# misc.net
KiCad netlist of a schematic drawn in Altium Designer
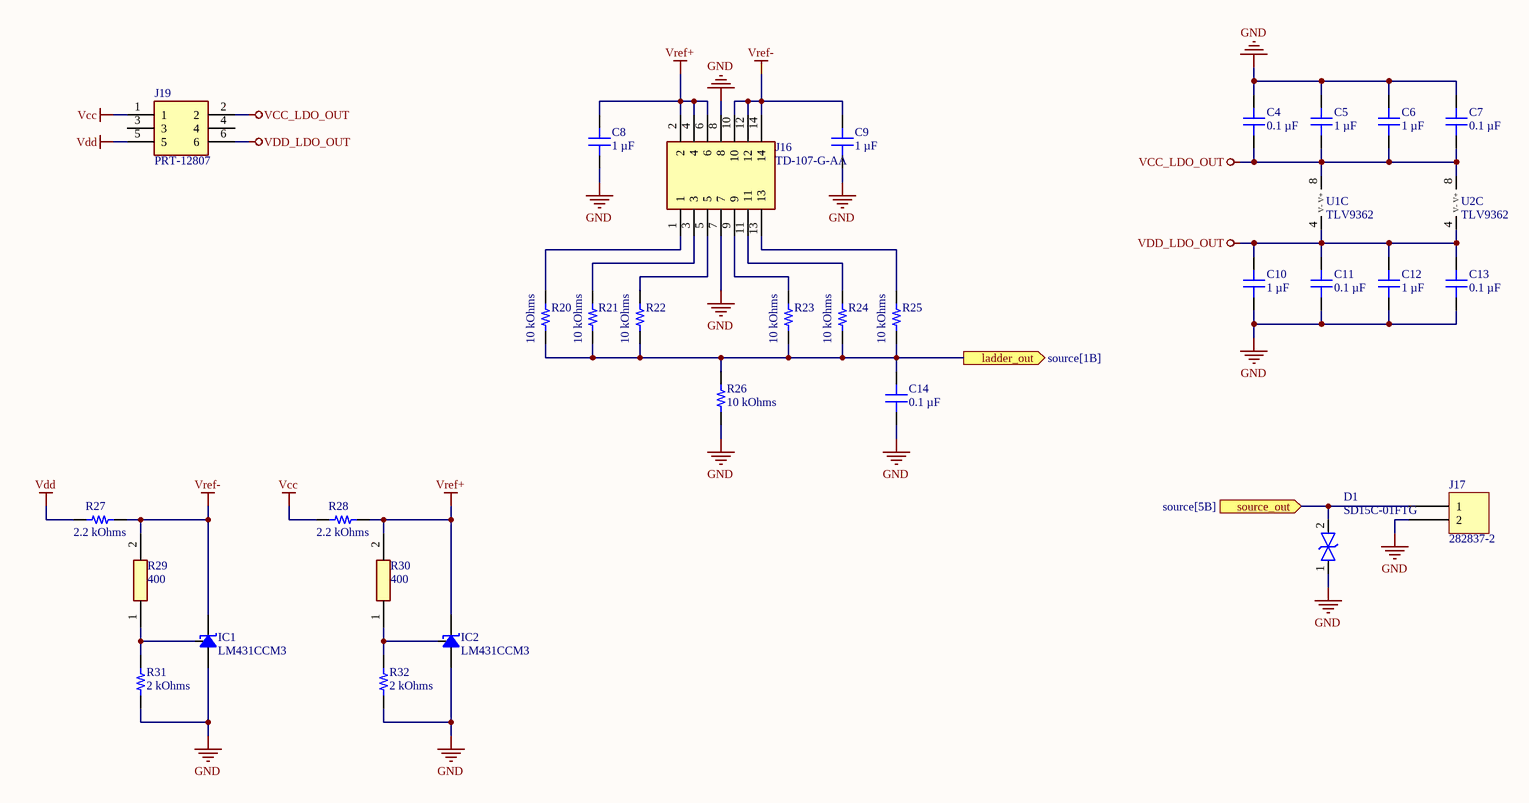
[diagram p0: misc.SchDoc]

(export (version "E")
  (design (tool "Eeschema 10.0.6"))
  (components
    (comp (ref "C4")
      (value "0.1 µF")
      (footprint "CAP 1206_3216 - 0.8MM")
      (description "CAP CER 0.1UF 50V X7R 1206")
      (fields
        (field (name "PART NUMBER") "885012208087")
        (field (name "CAPACITANCE") "0.1 µF")
        (field (name "MANUFACTURER") "Würth Elektronik")
      )
      (libsource (lib "Celestial Altium Library - altium_library") (part "Capacitor"))
    )
    (comp (ref "C5")
      (value "1 µF")
      (footprint "CAP 1206_3216 - 0.8MM")
      (description "CAP CER 1UF 50V X7R 1206")
      (fields
        (field (name "PART NUMBER") "885012208093")
        (field (name "CAPACITANCE") "1 µF")
        (field (name "MANUFACTURER") "Würth Elektronik")
      )
      (libsource (lib "Celestial Altium Library - altium_library") (part "Capacitor"))
    )
    (comp (ref "C6")
      (value "1 µF")
      (footprint "CAP 1206_3216 - 0.8MM")
      (description "CAP CER 1UF 50V X7R 1206")
      (fields
        (field (name "PART NUMBER") "885012208093")
        (field (name "CAPACITANCE") "1 µF")
        (field (name "MANUFACTURER") "Würth Elektronik")
      )
      (libsource (lib "Celestial Altium Library - altium_library") (part "Capacitor"))
    )
    (comp (ref "C7")
      (value "0.1 µF")
      (footprint "CAP 1206_3216 - 0.8MM")
      (description "CAP CER 0.1UF 50V X7R 1206")
      (fields
        (field (name "PART NUMBER") "885012208087")
        (field (name "CAPACITANCE") "0.1 µF")
        (field (name "MANUFACTURER") "Würth Elektronik")
      )
      (libsource (lib "Celestial Altium Library - altium_library") (part "Capacitor"))
    )
    (comp (ref "C8")
      (value "1 µF")
      (footprint "CAP 1206_3216 - 0.8MM")
      (description "CAP CER 1UF 50V X7R 1206")
      (fields
        (field (name "PART NUMBER") "885012208093")
        (field (name "CAPACITANCE") "1 µF")
        (field (name "MANUFACTURER") "Würth Elektronik")
      )
      (libsource (lib "Celestial Altium Library - altium_library") (part "Capacitor"))
    )
    (comp (ref "C9")
      (value "1 µF")
      (footprint "CAP 1206_3216 - 0.8MM")
      (description "CAP CER 1UF 50V X7R 1206")
      (fields
        (field (name "PART NUMBER") "885012208093")
        (field (name "CAPACITANCE") "1 µF")
        (field (name "MANUFACTURER") "Würth Elektronik")
      )
      (libsource (lib "Celestial Altium Library - altium_library") (part "Capacitor"))
    )
    (comp (ref "C10")
      (value "1 µF")
      (footprint "CAP 1206_3216 - 0.8MM")
      (description "CAP CER 1UF 50V X7R 1206")
      (fields
        (field (name "PART NUMBER") "885012208093")
        (field (name "CAPACITANCE") "1 µF")
        (field (name "MANUFACTURER") "Würth Elektronik")
      )
      (libsource (lib "Celestial Altium Library - altium_library") (part "Capacitor"))
    )
    (comp (ref "C11")
      (value "0.1 µF")
      (footprint "CAP 1206_3216 - 0.8MM")
      (description "CAP CER 0.1UF 50V X7R 1206")
      (fields
        (field (name "PART NUMBER") "885012208087")
        (field (name "CAPACITANCE") "0.1 µF")
        (field (name "MANUFACTURER") "Würth Elektronik")
      )
      (libsource (lib "Celestial Altium Library - altium_library") (part "Capacitor"))
    )
    (comp (ref "C12")
      (value "1 µF")
      (footprint "CAP 1206_3216 - 0.8MM")
      (description "CAP CER 1UF 50V X7R 1206")
      (fields
        (field (name "PART NUMBER") "885012208093")
        (field (name "CAPACITANCE") "1 µF")
        (field (name "MANUFACTURER") "Würth Elektronik")
      )
      (libsource (lib "Celestial Altium Library - altium_library") (part "Capacitor"))
    )
    (comp (ref "C13")
      (value "0.1 µF")
      (footprint "CAP 1206_3216 - 0.8MM")
      (description "CAP CER 0.1UF 50V X7R 1206")
      (fields
        (field (name "PART NUMBER") "885012208087")
        (field (name "CAPACITANCE") "0.1 µF")
        (field (name "MANUFACTURER") "Würth Elektronik")
      )
      (libsource (lib "Celestial Altium Library - altium_library") (part "Capacitor"))
    )
    (comp (ref "C14")
      (value "0.1 µF")
      (footprint "CAP 1206_3216 - 0.8MM")
      (description "CAP CER 0.1UF 50V X7R 1206")
      (fields
        (field (name "PART NUMBER") "885012208087")
        (field (name "CAPACITANCE") "0.1 µF")
        (field (name "MANUFACTURER") "Würth Elektronik")
      )
      (libsource (lib "Celestial Altium Library - altium_library") (part "Capacitor"))
    )
    (comp (ref "D1")
      (value "SD15C-01FTG")
      (footprint "za_koncar:SD15C01FTG")
      (description "TVS Diode (Bi-directional)")
      (fields (field (name "MOUSER PART NUMBER") "576-SD15C-01FTG"))
      (libsource (lib "za_koncar") (part "SD15C-01FTG"))
    )
    (comp (ref "IC1")
      (value "LM431CCM3")
      (footprint "SOT96P240X110-3N")
      (description "Integrated Circuit")
      (fields
        (field (name "MANUFACTURER_PART_NUMBER") "LM431CCM3/NOPB")
        (field (name "MOUSER PART NUMBER") "926-LM431CCM3/NOPB")
      )
      (libsource (lib "za_koncar") (part "LM431CCM3_NOPB"))
    )
    (comp (ref "IC2")
      (value "LM431CCM3")
      (footprint "SOT96P240X110-3N")
      (description "Integrated Circuit")
      (fields
        (field (name "MANUFACTURER_PART_NUMBER") "LM431CCM3/NOPB")
        (field (name "MOUSER PART NUMBER") "926-LM431CCM3/NOPB")
      )
      (libsource (lib "za_koncar") (part "LM431CCM3_NOPB"))
    )
    (comp (ref "J16")
      (value "TD-107-G-AA")
      (footprint "HDRV14W46P254_2X7_1778X508X818P")
      (description "Connector")
      (fields (field (name "MOUSER PART NUMBER") "200-TD107GAA"))
      (libsource (lib "za_koncar") (part "TD-107-G-AA"))
    )
    (comp (ref "J17")
      (value "282837-2")
      (footprint "TE 282837-2")
      (description "TERM BLK 2P SIDE ENT 5.08MM PCB")
      (fields (field (name "MANUFACTURER") "TE Connectivity AMP Connectors") (field (name "VOLTAGE") "300 V"))
      (libsource (lib "Celestial Altium Library - altium_library") (part "2 Pin"))
    )
    (comp (ref "J19")
      (value "PRT-12807")
      (footprint "HDRV6W82P254_2X3_762X500X884P")
      (description "Connector")
      (fields (field (name "MOUSER PART NUMBER") "474-PRT-12807"))
      (libsource (lib "za_koncar") (part "PRT-12807"))
    )
    (comp (ref "R20")
      (value "10 kOhms")
      (footprint "YAGEO RES 1206_3216")
      (description "RES SMD 10K OHM 1% 1/4W 1206")
      (fields (field (name "PART NUMBER") "RT1206FRE0710KL") (field (name "MANUFACTURER") "Yageo"))
      (libsource (lib "Celestial Altium Library - altium_library") (part "Resistor"))
    )
    (comp (ref "R21")
      (value "10 kOhms")
      (footprint "YAGEO RES 1206_3216")
      (description "RES SMD 10K OHM 1% 1/4W 1206")
      (fields (field (name "PART NUMBER") "RT1206FRE0710KL") (field (name "MANUFACTURER") "Yageo"))
      (libsource (lib "Celestial Altium Library - altium_library") (part "Resistor"))
    )
    (comp (ref "R22")
      (value "10 kOhms")
      (footprint "YAGEO RES 1206_3216")
      (description "RES SMD 10K OHM 1% 1/4W 1206")
      (fields (field (name "PART NUMBER") "RT1206FRE0710KL") (field (name "MANUFACTURER") "Yageo"))
      (libsource (lib "Celestial Altium Library - altium_library") (part "Resistor"))
    )
    (comp (ref "R23")
      (value "10 kOhms")
      (footprint "YAGEO RES 1206_3216")
      (description "RES SMD 10K OHM 1% 1/4W 1206")
      (fields (field (name "PART NUMBER") "RT1206FRE0710KL") (field (name "MANUFACTURER") "Yageo"))
      (libsource (lib "Celestial Altium Library - altium_library") (part "Resistor"))
    )
    (comp (ref "R24")
      (value "10 kOhms")
      (footprint "YAGEO RES 1206_3216")
      (description "RES SMD 10K OHM 1% 1/4W 1206")
      (fields (field (name "PART NUMBER") "RT1206FRE0710KL") (field (name "MANUFACTURER") "Yageo"))
      (libsource (lib "Celestial Altium Library - altium_library") (part "Resistor"))
    )
    (comp (ref "R25")
      (value "10 kOhms")
      (footprint "YAGEO RES 1206_3216")
      (description "RES SMD 10K OHM 1% 1/4W 1206")
      (fields (field (name "PART NUMBER") "RT1206FRE0710KL") (field (name "MANUFACTURER") "Yageo"))
      (libsource (lib "Celestial Altium Library - altium_library") (part "Resistor"))
    )
    (comp (ref "R26")
      (value "10 kOhms")
      (footprint "YAGEO RES 1206_3216")
      (description "RES SMD 10K OHM 1% 1/4W 1206")
      (fields (field (name "PART NUMBER") "RT1206FRE0710KL") (field (name "MANUFACTURER") "Yageo"))
      (libsource (lib "Celestial Altium Library - altium_library") (part "Resistor"))
    )
    (comp (ref "R27")
      (value "2.2 kOhms")
      (footprint "RES 1206_3216")
      (description "RES SMD 2.2K OHM 5% 1/4W 1206")
      (fields
        (field (name "PART NUMBER") "ERJ-8GEYJ222V")
        (field (name "MANUFACTURER") "Panasonic Electronic Components")
      )
      (libsource (lib "Celestial Altium Library - altium_library") (part "Resistor"))
    )
    (comp (ref "R28")
      (value "2.2 kOhms")
      (footprint "RES 1206_3216")
      (description "RES SMD 2.2K OHM 5% 1/4W 1206")
      (fields
        (field (name "PART NUMBER") "ERJ-8GEYJ222V")
        (field (name "MANUFACTURER") "Panasonic Electronic Components")
      )
      (libsource (lib "Celestial Altium Library - altium_library") (part "Resistor"))
    )
    (comp (ref "R29")
      (value "400")
      (footprint "RESC3116X65N")
      (description "Resistor")
      (fields
        (field (name "MANUFACTURER_PART_NUMBER") "RT1206BRD07400RL")
        (field (name "MOUSER PART NUMBER") "603-RT1206BRD07400RL")
      )
      (libsource (lib "za_koncar") (part "RT1206BRD07400RL"))
    )
    (comp (ref "R30")
      (value "400")
      (footprint "RESC3116X65N")
      (description "Resistor")
      (fields
        (field (name "MANUFACTURER_PART_NUMBER") "RT1206BRD07400RL")
        (field (name "MOUSER PART NUMBER") "603-RT1206BRD07400RL")
      )
      (libsource (lib "za_koncar") (part "RT1206BRD07400RL"))
    )
    (comp (ref "R31")
      (value "2 kOhms")
      (footprint "RES 1206_3216")
      (description "RES SMD 2K OHM 0.1% 1/4W 1206")
      (fields
        (field (name "PART NUMBER") "ERA-8AEB202V")
        (field (name "MANUFACTURER") "Panasonic Electronic Components")
      )
      (libsource (lib "Celestial Altium Library - altium_library") (part "Resistor"))
    )
    (comp (ref "R32")
      (value "2 kOhms")
      (footprint "RES 1206_3216")
      (description "RES SMD 2K OHM 0.1% 1/4W 1206")
      (fields
        (field (name "PART NUMBER") "ERA-8AEB202V")
        (field (name "MANUFACTURER") "Panasonic Electronic Components")
      )
      (libsource (lib "Celestial Altium Library - altium_library") (part "Resistor"))
    )
    (comp (ref "U1")
      (value "TLV9362")
      (footprint "SOIC8-127P600X175-8N")
      (description "TLV936x 10-MHz, 40-V, RRO, Operational Amplifie")
      (libsource (lib "za_koncar") (part "TLV9362"))
    )
    (comp (ref "U2")
      (value "TLV9362")
      (footprint "SOIC8-127P600X175-8N")
      (description "TLV936x 10-MHz, 40-V, RRO, Operational Amplifie")
      (libsource (lib "za_koncar") (part "TLV9362"))
    )
  )
  (nets
    (net (code "1") (name "/ladder_out") (class "Default")
      (node (ref "C14") (pin "1") (pinfunction "1_1") (pintype "passive"))
      (node (ref "R20") (pin "1") (pinfunction "1_1") (pintype "passive"))
      (node (ref "R21") (pin "1") (pinfunction "1_1") (pintype "passive"))
      (node (ref "R22") (pin "1") (pinfunction "1_1") (pintype "passive"))
      (node (ref "R23") (pin "1") (pinfunction "1_1") (pintype "passive"))
      (node (ref "R24") (pin "1") (pinfunction "1_1") (pintype "passive"))
      (node (ref "R25") (pin "1") (pinfunction "1_1") (pintype "passive"))
      (node (ref "R26") (pin "2") (pinfunction "2_2") (pintype "passive"))
    )
    (net (code "2") (name "/source_out") (class "Default")
      (node (ref "D1") (pin "2") (pinfunction "2_2") (pintype "passive"))
      (node (ref "J17") (pin "1") (pinfunction "1_1") (pintype "passive"))
    )
    (net (code "3") (name "GND") (class "Default")
      (node (ref "C10") (pin "2") (pinfunction "2_2") (pintype "passive"))
      (node (ref "C11") (pin "2") (pinfunction "2_2") (pintype "passive"))
      (node (ref "C12") (pin "2") (pinfunction "2_2") (pintype "passive"))
      (node (ref "C13") (pin "2") (pinfunction "2_2") (pintype "passive"))
      (node (ref "C14") (pin "2") (pinfunction "2_2") (pintype "passive"))
      (node (ref "C4") (pin "1") (pinfunction "1_1") (pintype "passive"))
      (node (ref "C5") (pin "1") (pinfunction "1_1") (pintype "passive"))
      (node (ref "C6") (pin "2") (pinfunction "2_2") (pintype "passive"))
      (node (ref "C7") (pin "2") (pinfunction "2_2") (pintype "passive"))
      (node (ref "C8") (pin "2") (pinfunction "2_2") (pintype "passive"))
      (node (ref "C9") (pin "1") (pinfunction "1_1") (pintype "passive"))
      (node (ref "D1") (pin "1") (pinfunction "1_1") (pintype "passive"))
      (node (ref "IC1") (pin "2") (pinfunction "Anode_2") (pintype "passive"))
      (node (ref "IC2") (pin "2") (pinfunction "Anode_2") (pintype "passive"))
      (node (ref "J16") (pin "7") (pinfunction "7_7") (pintype "passive"))
      (node (ref "J16") (pin "8") (pinfunction "8_8") (pintype "passive"))
      (node (ref "J17") (pin "2") (pinfunction "2_2") (pintype "passive"))
      (node (ref "R26") (pin "1") (pinfunction "1_1") (pintype "passive"))
      (node (ref "R31") (pin "1") (pinfunction "1_1") (pintype "passive"))
      (node (ref "R32") (pin "1") (pinfunction "1_1") (pintype "passive"))
    )
    (net (code "4") (name "Net-(IC1-Ref)") (class "Default")
      (node (ref "IC1") (pin "3") (pinfunction "Ref_3") (pintype "passive"))
      (node (ref "R29") (pin "1") (pinfunction "1_1") (pintype "passive"))
      (node (ref "R31") (pin "2") (pinfunction "2_2") (pintype "passive"))
    )
    (net (code "5") (name "Net-(IC2-Ref)") (class "Default")
      (node (ref "IC2") (pin "3") (pinfunction "Ref_3") (pintype "passive"))
      (node (ref "R30") (pin "1") (pinfunction "1_1") (pintype "passive"))
      (node (ref "R32") (pin "2") (pinfunction "2_2") (pintype "passive"))
    )
    (net (code "6") (name "Net-(J16-Pad1)") (class "Default")
      (node (ref "J16") (pin "1") (pinfunction "1_1") (pintype "passive"))
      (node (ref "R20") (pin "2") (pinfunction "2_2") (pintype "passive"))
    )
    (net (code "7") (name "Net-(J16-Pad3)") (class "Default")
      (node (ref "J16") (pin "3") (pinfunction "3_3") (pintype "passive"))
      (node (ref "R21") (pin "2") (pinfunction "2_2") (pintype "passive"))
    )
    (net (code "8") (name "Net-(J16-Pad5)") (class "Default")
      (node (ref "J16") (pin "5") (pinfunction "5_5") (pintype "passive"))
      (node (ref "R22") (pin "2") (pinfunction "2_2") (pintype "passive"))
    )
    (net (code "9") (name "Net-(J16-Pad9)") (class "Default")
      (node (ref "J16") (pin "9") (pinfunction "9_9") (pintype "passive"))
      (node (ref "R23") (pin "2") (pinfunction "2_2") (pintype "passive"))
    )
    (net (code "10") (name "Net-(J16-Pad11)") (class "Default")
      (node (ref "J16") (pin "11") (pinfunction "11_11") (pintype "passive"))
      (node (ref "R24") (pin "2") (pinfunction "2_2") (pintype "passive"))
    )
    (net (code "11") (name "Net-(J16-Pad13)") (class "Default")
      (node (ref "J16") (pin "13") (pinfunction "13_13") (pintype "passive"))
      (node (ref "R25") (pin "2") (pinfunction "2_2") (pintype "passive"))
    )
    (net (code "12") (name "VCC_LDO_OUT") (class "Default")
      (node (ref "C4") (pin "2") (pinfunction "2_2") (pintype "passive"))
      (node (ref "C5") (pin "2") (pinfunction "2_2") (pintype "passive"))
      (node (ref "C6") (pin "1") (pinfunction "1_1") (pintype "passive"))
      (node (ref "C7") (pin "1") (pinfunction "1_1") (pintype "passive"))
      (node (ref "J19") (pin "2") (pinfunction "2_2") (pintype "passive"))
      (node (ref "U1") (pin "8") (pinfunction "V+_8") (pintype "power_in"))
      (node (ref "U2") (pin "8") (pinfunction "V+_8") (pintype "power_in"))
    )
    (net (code "13") (name "VDD_LDO_OUT") (class "Default")
      (node (ref "C10") (pin "1") (pinfunction "1_1") (pintype "passive"))
      (node (ref "C11") (pin "1") (pinfunction "1_1") (pintype "passive"))
      (node (ref "C12") (pin "1") (pinfunction "1_1") (pintype "passive"))
      (node (ref "C13") (pin "1") (pinfunction "1_1") (pintype "passive"))
      (node (ref "J19") (pin "6") (pinfunction "6_6") (pintype "passive"))
      (node (ref "U1") (pin "4") (pinfunction "V-_4") (pintype "power_in"))
      (node (ref "U2") (pin "4") (pinfunction "V-_4") (pintype "power_in"))
    )
    (net (code "14") (name "Vcc") (class "Default")
      (node (ref "J19") (pin "1") (pinfunction "1_1") (pintype "passive"))
      (node (ref "R28") (pin "1") (pinfunction "1_1") (pintype "passive"))
    )
    (net (code "15") (name "Vdd") (class "Default")
      (node (ref "J19") (pin "5") (pinfunction "5_5") (pintype "passive"))
      (node (ref "R27") (pin "1") (pinfunction "1_1") (pintype "passive"))
    )
    (net (code "16") (name "Vref+") (class "Default")
      (node (ref "C8") (pin "1") (pinfunction "1_1") (pintype "passive"))
      (node (ref "IC2") (pin "1") (pinfunction "Cathode_1") (pintype "passive"))
      (node (ref "J16") (pin "2") (pinfunction "2_2") (pintype "passive"))
      (node (ref "J16") (pin "4") (pinfunction "4_4") (pintype "passive"))
      (node (ref "J16") (pin "6") (pinfunction "6_6") (pintype "passive"))
      (node (ref "R28") (pin "2") (pinfunction "2_2") (pintype "passive"))
      (node (ref "R30") (pin "2") (pinfunction "2_2") (pintype "passive"))
    )
    (net (code "17") (name "Vref-") (class "Default")
      (node (ref "C9") (pin "2") (pinfunction "2_2") (pintype "passive"))
      (node (ref "IC1") (pin "1") (pinfunction "Cathode_1") (pintype "passive"))
      (node (ref "J16") (pin "10") (pinfunction "10_10") (pintype "passive"))
      (node (ref "J16") (pin "12") (pinfunction "12_12") (pintype "passive"))
      (node (ref "J16") (pin "14") (pinfunction "14_14") (pintype "passive"))
      (node (ref "R27") (pin "2") (pinfunction "2_2") (pintype "passive"))
      (node (ref "R29") (pin "2") (pinfunction "2_2") (pintype "passive"))
    )
    (net (code "18") (name "unconnected-(J19-Pad3)") (class "Default")
      (node (ref "J19") (pin "3") (pinfunction "3_3") (pintype "passive"))
    )
    (net (code "19") (name "unconnected-(J19-Pad4)") (class "Default")
      (node (ref "J19") (pin "4") (pinfunction "4_4") (pintype "passive"))
    )
  )
)
